# LEDPoet.net
KiCad netlist of a schematic drawn in EAGLE
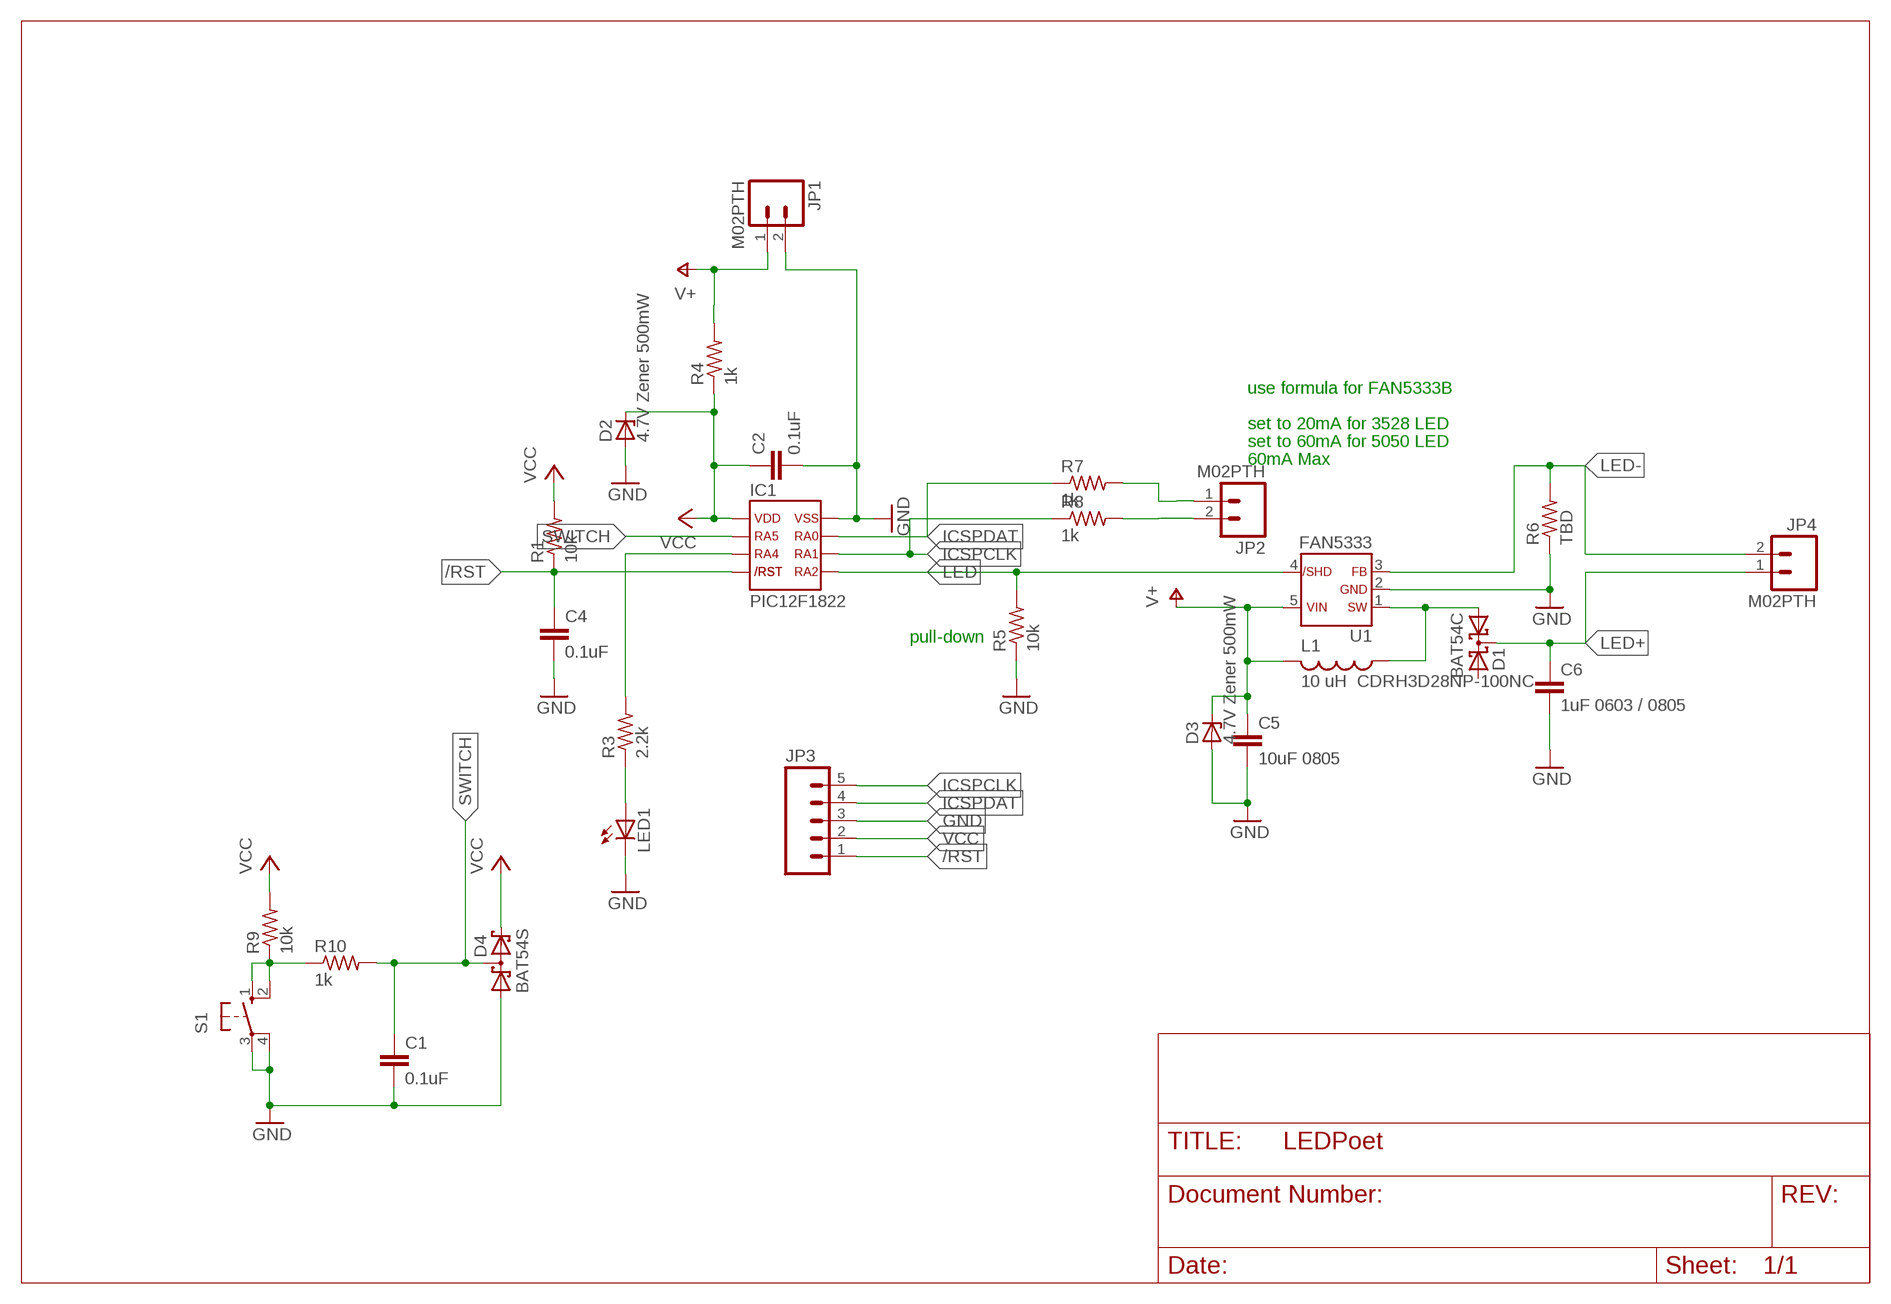
[diagram p0: schematic, sheet 1]

(export (version "E")
  (design (tool "Eeschema 10.0.6"))
  (components
    (comp (ref "C1")
      (value "0.1uF")
      (footprint "eagle-import:C0603(1608)")
      (libsource (lib "eagle-import") (part "WaterDrop_C0603(1608)"))
    )
    (comp (ref "C2")
      (value "0.1uF")
      (footprint "eagle-import:C0603(1608)")
      (libsource (lib "eagle-import") (part "WaterDrop_C0603(1608)"))
    )
    (comp (ref "C4")
      (value "0.1uF")
      (footprint "eagle-import:C0603(1608)")
      (libsource (lib "eagle-import") (part "WaterDrop_C0603(1608)"))
    )
    (comp (ref "C5")
      (value "10uF 0805")
      (footprint "eagle-import:C0805(2012)")
      (libsource (lib "eagle-import") (part "C0805(2012)"))
    )
    (comp (ref "C6")
      (value "1uF 0603 / 0805")
      (footprint "eagle-import:C0805(2012)")
      (libsource (lib "eagle-import") (part "C0805(2012)"))
    )
    (comp (ref "D1")
      (value "BAT54C")
      (footprint "eagle-import:SOT23")
      (libsource (lib "eagle-import") (part "BAT54C"))
    )
    (comp (ref "D2")
      (value "4.7V Zener 500mW")
      (footprint "eagle-import:SOD-123")
      (libsource (lib "eagle-import") (part "ZENER-DIODE"))
    )
    (comp (ref "D3")
      (value "4.7V Zener 500mW")
      (footprint "eagle-import:SOD-123")
      (libsource (lib "eagle-import") (part "ZENER-DIODE"))
    )
    (comp (ref "D4")
      (value "BAT54S")
      (footprint "eagle-import:SOT23")
      (libsource (lib "eagle-import") (part "BAT54S"))
    )
    (comp (ref "IC1")
      (value "PIC12F1822")
      (footprint "eagle-import:SO8")
      (libsource (lib "eagle-import") (part "PIC12F1822"))
    )
    (comp (ref "JP1")
      (value "M02PTH")
      (footprint "eagle-import:1X02")
      (libsource (lib "eagle-import") (part "M02PTH"))
    )
    (comp (ref "JP2")
      (value "M02PTH")
      (footprint "eagle-import:1X02")
      (libsource (lib "eagle-import") (part "M02PTH"))
    )
    (comp (ref "JP3")
      (value "M05PTH")
      (footprint "eagle-import:1X05")
      (libsource (lib "eagle-import") (part "M05PTH"))
    )
    (comp (ref "JP4")
      (value "M02PTH")
      (footprint "eagle-import:1X02")
      (libsource (lib "eagle-import") (part "M02PTH"))
    )
    (comp (ref "L1")
      (value "10 uH CDRH3D28NP-100NC")
      (footprint "eagle-import:CDRH3D18")
      (libsource (lib "eagle-import") (part "L"))
    )
    (comp (ref "LED1")
      (value "LED0603")
      (footprint "eagle-import:LED-0603")
      (libsource (lib "eagle-import") (part "LED0603"))
    )
    (comp (ref "R1")
      (value "10k")
      (footprint "eagle-import:R0603(1608)")
      (libsource (lib "eagle-import") (part "R0603(1608)"))
    )
    (comp (ref "R3")
      (value "2.2k")
      (footprint "eagle-import:R0603(1608)")
      (libsource (lib "eagle-import") (part "R0603(1608)"))
    )
    (comp (ref "R4")
      (value "1k")
      (footprint "eagle-import:R0603(1608)")
      (libsource (lib "eagle-import") (part "R0603(1608)"))
    )
    (comp (ref "R5")
      (value "10k")
      (footprint "eagle-import:R0603(1608)")
      (libsource (lib "eagle-import") (part "R0603(1608)"))
    )
    (comp (ref "R6")
      (value "TBD")
      (footprint "eagle-import:R0603(1608)")
      (libsource (lib "eagle-import") (part "R0603(1608)"))
    )
    (comp (ref "R7")
      (value "1k")
      (footprint "eagle-import:R0603(1608)")
      (libsource (lib "eagle-import") (part "R0603(1608)"))
    )
    (comp (ref "R8")
      (value "1k")
      (footprint "eagle-import:R0603(1608)")
      (libsource (lib "eagle-import") (part "R0603(1608)"))
    )
    (comp (ref "R9")
      (value "10k")
      (footprint "eagle-import:R0603(1608)")
      (libsource (lib "eagle-import") (part "R0603(1608)"))
    )
    (comp (ref "R10")
      (value "1k")
      (footprint "eagle-import:R0603(1608)")
      (libsource (lib "eagle-import") (part "R0603(1608)"))
    )
    (comp (ref "S1")
      (value "40-XX")
      (footprint "eagle-import:B3F-40XX")
      (fields (field (name "MF") "OMRON COMPONENTS USA") (field (name "MPN") "B3F-4000"))
      (libsource (lib "eagle-import") (part "40-XX"))
    )
    (comp (ref "U1")
      (value "FAN5333")
      (footprint "eagle-import:SOT-23-5")
      (libsource (lib "eagle-import") (part "FAN5333"))
    )
  )
  (nets
    (net (code "1") (name "GND") (class "Default")
      (node (ref "C1") (pin "2") (pinfunction "2_2") (pintype "passive"))
      (node (ref "C2") (pin "2") (pinfunction "2_2") (pintype "passive"))
      (node (ref "C4") (pin "2") (pinfunction "2_2") (pintype "passive"))
      (node (ref "C5") (pin "2") (pinfunction "2_2") (pintype "passive"))
      (node (ref "C6") (pin "2") (pinfunction "2_2") (pintype "passive"))
      (node (ref "D2") (pin "A") (pinfunction "A_A") (pintype "passive"))
      (node (ref "D3") (pin "A") (pinfunction "A_A") (pintype "passive"))
      (node (ref "D4") (pin "1") (pinfunction "A1_1") (pintype "passive"))
      (node (ref "IC1") (pin "8") (pinfunction "P$8_8") (pintype "power_in"))
      (node (ref "JP1") (pin "2") (pinfunction "2_2") (pintype "passive"))
      (node (ref "JP3") (pin "3") (pinfunction "3_3") (pintype "passive"))
      (node (ref "LED1") (pin "C") (pinfunction "C_C") (pintype "passive"))
      (node (ref "R5") (pin "1") (pinfunction "1_1") (pintype "passive"))
      (node (ref "R6") (pin "1") (pinfunction "1_1") (pintype "passive"))
      (node (ref "S1") (pin "3") (pinfunction "P_3") (pintype "passive"))
      (node (ref "S1") (pin "4") (pinfunction "P1_4") (pintype "passive"))
      (node (ref "U1") (pin "2") (pinfunction "2_2") (pintype "bidirectional"))
    )
    (net (code "2") (name "ICSPCLK") (class "Default")
      (node (ref "IC1") (pin "6") (pinfunction "P$6_6") (pintype "bidirectional"))
      (node (ref "JP3") (pin "5") (pinfunction "5_5") (pintype "passive"))
      (node (ref "R8") (pin "1") (pinfunction "1_1") (pintype "passive"))
    )
    (net (code "3") (name "ICSPDAT") (class "Default")
      (node (ref "IC1") (pin "7") (pinfunction "P$7_7") (pintype "bidirectional"))
      (node (ref "JP3") (pin "4") (pinfunction "4_4") (pintype "passive"))
      (node (ref "R7") (pin "1") (pinfunction "1_1") (pintype "passive"))
    )
    (net (code "4") (name "LED") (class "Default")
      (node (ref "IC1") (pin "5") (pinfunction "P$5_5") (pintype "bidirectional"))
      (node (ref "R5") (pin "2") (pinfunction "2_2") (pintype "passive"))
      (node (ref "U1") (pin "4") (pinfunction "4_4") (pintype "bidirectional"))
    )
    (net (code "5") (name "LED+") (class "Default")
      (node (ref "C6") (pin "1") (pinfunction "1_1") (pintype "passive"))
      (node (ref "D1") (pin "3") (pinfunction "CC_3") (pintype "passive"))
      (node (ref "JP4") (pin "1") (pinfunction "1_1") (pintype "passive"))
    )
    (net (code "6") (name "LED-") (class "Default")
      (node (ref "JP4") (pin "2") (pinfunction "2_2") (pintype "passive"))
      (node (ref "R6") (pin "2") (pinfunction "2_2") (pintype "passive"))
      (node (ref "U1") (pin "3") (pinfunction "3_3") (pintype "bidirectional"))
    )
    (net (code "7") (name "Net-(D1-A1)") (class "Default")
      (node (ref "D1") (pin "1") (pinfunction "A1_1") (pintype "passive"))
      (node (ref "L1") (pin "P$1") (pinfunction "1_P$1") (pintype "passive"))
      (node (ref "U1") (pin "1") (pinfunction "1_1") (pintype "bidirectional"))
    )
    (net (code "8") (name "Net-(IC1-P$3)") (class "Default")
      (node (ref "IC1") (pin "3") (pinfunction "P$3_3") (pintype "bidirectional"))
      (node (ref "R3") (pin "2") (pinfunction "2_2") (pintype "passive"))
    )
    (net (code "9") (name "Net-(JP2-Pad1)") (class "Default")
      (node (ref "JP2") (pin "1") (pinfunction "1_1") (pintype "passive"))
      (node (ref "R7") (pin "2") (pinfunction "2_2") (pintype "passive"))
    )
    (net (code "10") (name "Net-(JP2-Pad2)") (class "Default")
      (node (ref "JP2") (pin "2") (pinfunction "2_2") (pintype "passive"))
      (node (ref "R8") (pin "2") (pinfunction "2_2") (pintype "passive"))
    )
    (net (code "11") (name "Net-(LED1-PadA)") (class "Default")
      (node (ref "LED1") (pin "A") (pinfunction "A_A") (pintype "passive"))
      (node (ref "R3") (pin "1") (pinfunction "1_1") (pintype "passive"))
    )
    (net (code "12") (name "Net-(S1-S)") (class "Default")
      (node (ref "R10") (pin "1") (pinfunction "1_1") (pintype "passive"))
      (node (ref "R9") (pin "1") (pinfunction "1_1") (pintype "passive"))
      (node (ref "S1") (pin "1") (pinfunction "S_1") (pintype "passive"))
      (node (ref "S1") (pin "2") (pinfunction "S1_2") (pintype "passive"))
    )
    (net (code "13") (name "SWITCH") (class "Default")
      (node (ref "C1") (pin "1") (pinfunction "1_1") (pintype "passive"))
      (node (ref "D4") (pin "3") (pinfunction "C1A2_3") (pintype "passive"))
      (node (ref "IC1") (pin "2") (pinfunction "P$2_2") (pintype "bidirectional"))
      (node (ref "R10") (pin "2") (pinfunction "2_2") (pintype "passive"))
    )
    (net (code "14") (name "V+") (class "Default")
      (node (ref "C5") (pin "1") (pinfunction "1_1") (pintype "passive"))
      (node (ref "D3") (pin "C") (pinfunction "C_C") (pintype "passive"))
      (node (ref "JP1") (pin "1") (pinfunction "1_1") (pintype "passive"))
      (node (ref "L1") (pin "P$2") (pinfunction "2_P$2") (pintype "passive"))
      (node (ref "R4") (pin "2") (pinfunction "2_2") (pintype "passive"))
      (node (ref "U1") (pin "5") (pinfunction "5_5") (pintype "bidirectional"))
    )
    (net (code "15") (name "VCC") (class "Default")
      (node (ref "C2") (pin "1") (pinfunction "1_1") (pintype "passive"))
      (node (ref "D2") (pin "C") (pinfunction "C_C") (pintype "passive"))
      (node (ref "D4") (pin "2") (pinfunction "C2_2") (pintype "passive"))
      (node (ref "IC1") (pin "1") (pinfunction "P$1_1") (pintype "power_in"))
      (node (ref "JP3") (pin "2") (pinfunction "2_2") (pintype "passive"))
      (node (ref "R1") (pin "2") (pinfunction "2_2") (pintype "passive"))
      (node (ref "R4") (pin "1") (pinfunction "1_1") (pintype "passive"))
      (node (ref "R9") (pin "2") (pinfunction "2_2") (pintype "passive"))
    )
    (net (code "16") (name "unconnected-(D1-A2-Pad2)") (class "Default")
      (node (ref "D1") (pin "2") (pinfunction "A2_2") (pintype "passive"))
    )
    (net (code "17") (name "{slash}RST") (class "Default")
      (node (ref "C4") (pin "1") (pinfunction "1_1") (pintype "passive"))
      (node (ref "IC1") (pin "4") (pinfunction "P$4_4") (pintype "bidirectional"))
      (node (ref "JP3") (pin "1") (pinfunction "1_1") (pintype "passive"))
      (node (ref "R1") (pin "1") (pinfunction "1_1") (pintype "passive"))
    )
  )
)
